# Sheet1.net
KiCad netlist of a schematic drawn in Altium Designer
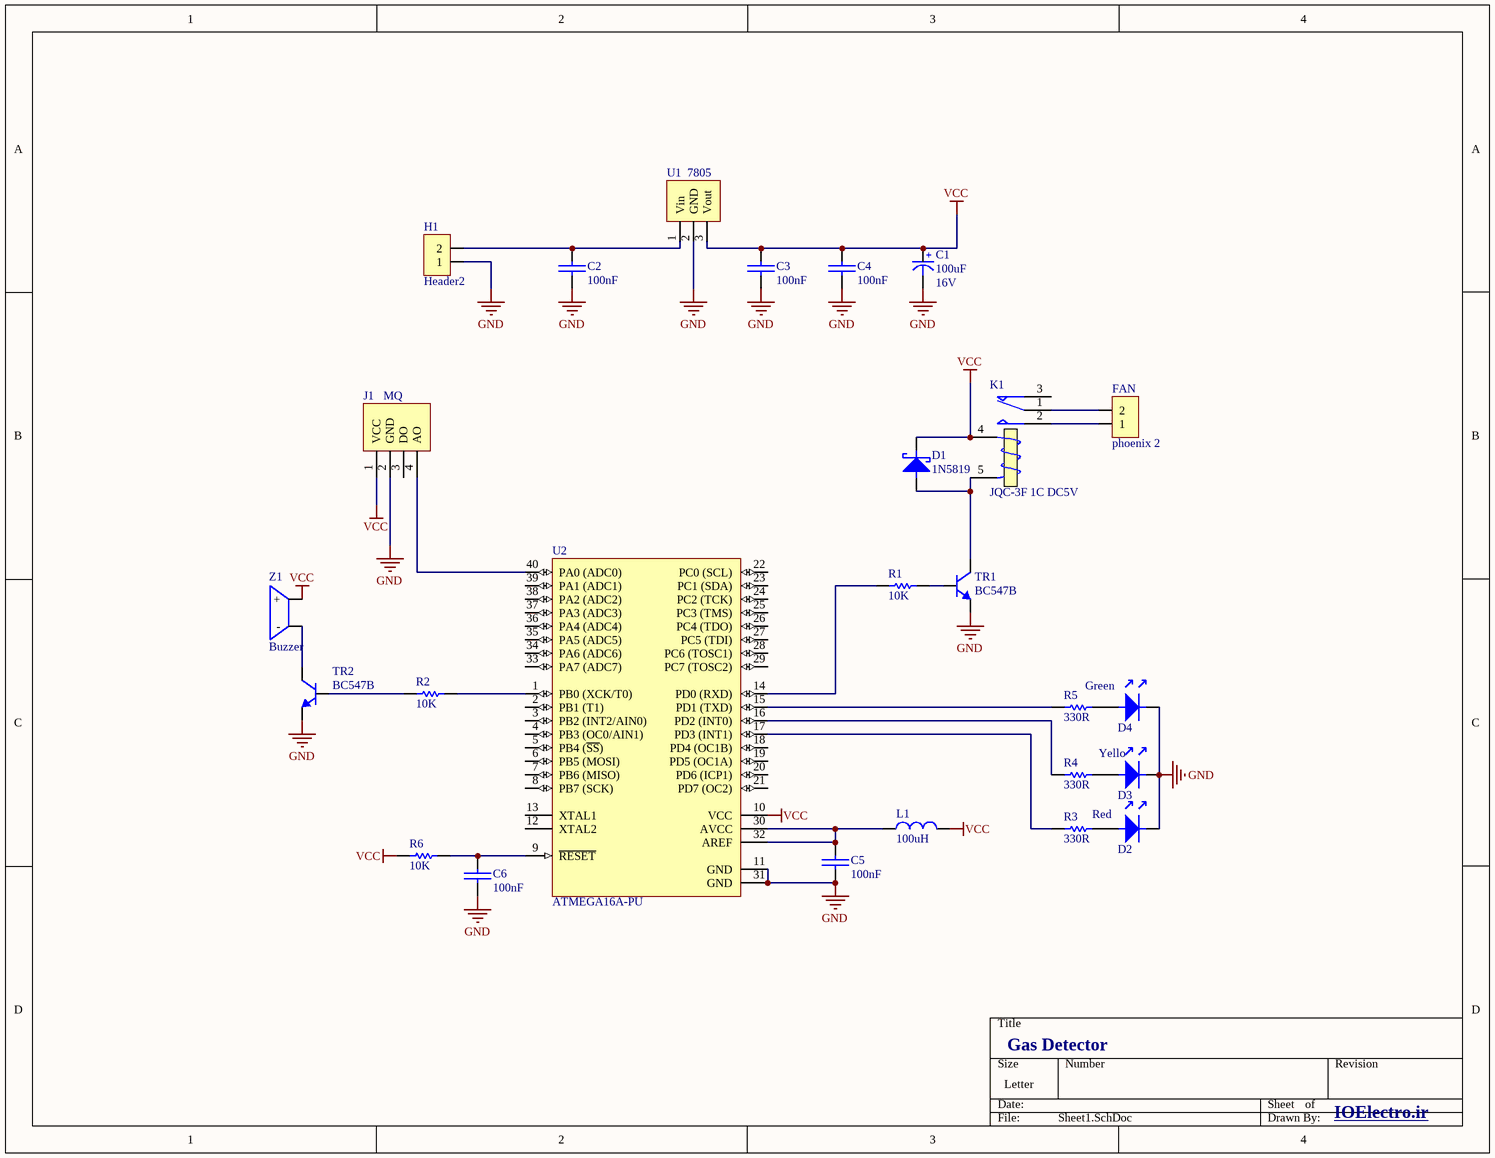
[diagram p0: Sheet1.SchDoc]

(export (version "E")
  (design (tool "Eeschema 10.0.6"))
  (components
    (comp (ref "C1")
      (value "100uF")
      (footprint "cap 03")
      (description "Polar Capacitor")
      (fields (field (name "VOLTAGE") "16V") (field (name "DESIGNER") "Saeid Jorablo"))
      (libsource (lib "My Library") (part "Cap-Polar"))
    )
    (comp (ref "C2")
      (value "100nF")
      (footprint "Cap - 100nF")
      (description "Bipolar Capacitor")
      (fields (field (name "VOLTAGE") "100V") (field (name "DESIGNER") "Saeid Jorablo"))
      (libsource (lib "My Library") (part "Cap-Bipolar"))
    )
    (comp (ref "C3")
      (value "100nF")
      (footprint "Cap - 100nF")
      (description "Bipolar Capacitor")
      (fields (field (name "VOLTAGE") "100V") (field (name "DESIGNER") "Saeid Jorablo"))
      (libsource (lib "My Library") (part "Cap-Bipolar"))
    )
    (comp (ref "C4")
      (value "100nF")
      (footprint "Cap - 100nF")
      (description "Bipolar Capacitor")
      (fields (field (name "VOLTAGE") "100V") (field (name "DESIGNER") "Saeid Jorablo"))
      (libsource (lib "My Library") (part "Cap-Bipolar"))
    )
    (comp (ref "C5")
      (value "100nF")
      (footprint "Cap - 100nF")
      (description "Bipolar Capacitor")
      (fields (field (name "VOLTAGE") "100V") (field (name "DESIGNER") "Saeid Jorablo"))
      (libsource (lib "My Library") (part "Cap-Bipolar"))
    )
    (comp (ref "C6")
      (value "100nF")
      (footprint "Cap - 100nF")
      (description "Bipolar Capacitor")
      (fields (field (name "VOLTAGE") "100V") (field (name "DESIGNER") "Saeid Jorablo"))
      (libsource (lib "My Library") (part "Cap-Bipolar"))
    )
    (comp (ref "D1")
      (value "1N5819")
      (footprint "Diode_Axial_Lead")
      (description "1N58 Series 600 mV 1 A 40 V Max Reverse Voltage Schottky Barrier Rectifier-DO-41")
      (fields (field (name "MANUFACTURER") "ON Semiconductor / Fairchild"))
      (libsource (lib "IOElectro") (part "1N5819"))
    )
    (comp (ref "D2") (value "Red") (footprint "LED5MM") (libsource (lib "MyLib") (part "LED")))
    (comp (ref "D3") (value "Yello") (footprint "LED5MM") (libsource (lib "MyLib") (part "LED")))
    (comp (ref "D4") (value "Green") (footprint "LED5MM") (libsource (lib "MyLib") (part "LED")))
    (comp (ref "FAN") (value "phoenix 2") (footprint "phonix-2") (libsource (lib "MyLib") (part "CONN-PH-2")))
    (comp (ref "H1") (value "Header2") (footprint "HEADER-2") (libsource (lib "MyLib") (part "HEADER-2")))
    (comp (ref "J1") (value "MQ") (footprint "MQ") (libsource (lib "MyLib") (part "MQ")))
    (comp (ref "K1")
      (value "JQC-3F 1C DC5V")
      (footprint "JQC-3F(T73)")
      (description "Relay Milon 5V 1Contact T73")
      (libsource (lib "IOElectro") (part "JQC-3F 1C DC5V"))
    )
    (comp (ref "L1") (value "100uH") (footprint "IND-DIP") (libsource (lib "MyLib") (part "Inductor")))
    (comp (ref "R1")
      (value "10K")
      (footprint "RES-DIP")
      (description "1/4 W DIP")
      (libsource (lib "Schlib") (part "RES-Dip"))
    )
    (comp (ref "R2")
      (value "10K")
      (footprint "RES-DIP")
      (description "1/4 W DIP")
      (libsource (lib "Schlib") (part "RES-Dip"))
    )
    (comp (ref "R3")
      (value "330R")
      (footprint "RES-DIP")
      (description "1/4 W DIP")
      (libsource (lib "Schlib") (part "RES-Dip"))
    )
    (comp (ref "R4")
      (value "330R")
      (footprint "RES-DIP")
      (description "1/4 W DIP")
      (libsource (lib "Schlib") (part "RES-Dip"))
    )
    (comp (ref "R5")
      (value "330R")
      (footprint "RES-DIP")
      (description "1/4 W DIP")
      (libsource (lib "Schlib") (part "RES-Dip"))
    )
    (comp (ref "R6")
      (value "10K")
      (footprint "RES-DIP")
      (description "1/4 W DIP")
      (libsource (lib "Schlib") (part "RES-Dip"))
    )
    (comp (ref "TR1")
      (value "BC547B")
      (footprint "TO-92")
      (fields (field (name "MANUFACTURER") "ON Semiconductor / Fairchild") (field (name "VOLTAGE") "40V"))
      (libsource (lib "MyLib") (part "BC547B"))
    )
    (comp (ref "TR2")
      (value "BC547B")
      (footprint "TO-92")
      (fields (field (name "MANUFACTURER") "ON Semiconductor / Fairchild") (field (name "VOLTAGE") "40V"))
      (libsource (lib "MyLib") (part "BC547B"))
    )
    (comp (ref "U1") (value "7805") (footprint "TO-220") (libsource (lib "MyLib") (part "7805")))
    (comp (ref "U2")
      (value "ATMEGA16A-PU")
      (footprint "DIP-40")
      (description "MCU 8-Bit ATmega AVR RISC 16KB Flash 3.3V/5V 40-Pin PDIP")
      (fields (field (name "MANUFACTURER") "Microchip / Atmel"))
      (libsource (lib "IOElectro") (part "ATMEGA16A-PU"))
    )
    (comp (ref "Z1") (value "Buzzer") (footprint "BUZZER-TMB12A05") (libsource (lib "MyLib") (part "BUZZER")))
  )
  (nets
    (net (code "1") (name "GND") (class "Default")
      (node (ref "C1") (pin "2") (pinfunction "-_2") (pintype "passive"))
      (node (ref "C2") (pin "2") (pinfunction "-_2") (pintype "passive"))
      (node (ref "C3") (pin "2") (pinfunction "-_2") (pintype "passive"))
      (node (ref "C4") (pin "2") (pinfunction "-_2") (pintype "passive"))
      (node (ref "C5") (pin "2") (pinfunction "-_2") (pintype "passive"))
      (node (ref "C6") (pin "2") (pinfunction "-_2") (pintype "passive"))
      (node (ref "D2") (pin "K") (pinfunction "K_K") (pintype "passive"))
      (node (ref "D3") (pin "K") (pinfunction "K_K") (pintype "passive"))
      (node (ref "D4") (pin "K") (pinfunction "K_K") (pintype "passive"))
      (node (ref "H1") (pin "1") (pinfunction "1_1") (pintype "passive"))
      (node (ref "J1") (pin "2") (pinfunction "GND_2") (pintype "passive"))
      (node (ref "TR1") (pin "3") (pinfunction "E_3") (pintype "passive"))
      (node (ref "TR2") (pin "3") (pinfunction "E_3") (pintype "passive"))
      (node (ref "U1") (pin "2") (pinfunction "GND_2") (pintype "passive"))
      (node (ref "U2") (pin "11") (pinfunction "GND_11") (pintype "power_in"))
      (node (ref "U2") (pin "31") (pinfunction "GND_31") (pintype "power_in"))
    )
    (net (code "2") (name "Net-(C2-+)") (class "Default")
      (node (ref "C2") (pin "1") (pinfunction "+_1") (pintype "passive"))
      (node (ref "H1") (pin "2") (pinfunction "2_2") (pintype "passive"))
      (node (ref "U1") (pin "1") (pinfunction "Vin_1") (pintype "passive"))
    )
    (net (code "3") (name "Net-(C5-+)") (class "Default")
      (node (ref "C5") (pin "1") (pinfunction "+_1") (pintype "passive"))
      (node (ref "L1") (pin "2") (pinfunction "2_2") (pintype "passive"))
      (node (ref "U2") (pin "30") (pinfunction "AVCC_30") (pintype "power_in"))
      (node (ref "U2") (pin "32") (pinfunction "AREF_32") (pintype "power_in"))
    )
    (net (code "4") (name "Net-(C6-+)") (class "Default")
      (node (ref "C6") (pin "1") (pinfunction "+_1") (pintype "passive"))
      (node (ref "R6") (pin "2") (pinfunction "2_2") (pintype "passive"))
      (node (ref "U2") (pin "9") (pinfunction "~{RESET}_9") (pintype "input"))
    )
    (net (code "5") (name "Net-(D2-PadA)") (class "Default")
      (node (ref "D2") (pin "A") (pinfunction "A_A") (pintype "passive"))
      (node (ref "R3") (pin "2") (pinfunction "2_2") (pintype "passive"))
    )
    (net (code "6") (name "Net-(D3-PadA)") (class "Default")
      (node (ref "D3") (pin "A") (pinfunction "A_A") (pintype "passive"))
      (node (ref "R4") (pin "2") (pinfunction "2_2") (pintype "passive"))
    )
    (net (code "7") (name "Net-(D4-PadA)") (class "Default")
      (node (ref "D4") (pin "A") (pinfunction "A_A") (pintype "passive"))
      (node (ref "R5") (pin "2") (pinfunction "2_2") (pintype "passive"))
    )
    (net (code "8") (name "Net-(J1-AO)") (class "Default")
      (node (ref "J1") (pin "4") (pinfunction "AO_4") (pintype "passive"))
      (node (ref "U2") (pin "40") (pinfunction "PA0_(ADC0)_40") (pintype "bidirectional"))
    )
    (net (code "9") (name "Net-(K1-COM)") (class "Default")
      (node (ref "FAN") (pin "2") (pinfunction "2_2") (pintype "passive"))
      (node (ref "K1") (pin "1") (pinfunction "COM_1") (pintype "passive"))
    )
    (net (code "10") (name "Net-(K1-NO)") (class "Default")
      (node (ref "FAN") (pin "1") (pinfunction "1_1") (pintype "passive"))
      (node (ref "K1") (pin "2") (pinfunction "NO_2") (pintype "passive"))
    )
    (net (code "11") (name "Net-(K1-T2)") (class "Default")
      (node (ref "D1") (pin "A") (pinfunction "A_A") (pintype "passive"))
      (node (ref "K1") (pin "5") (pinfunction "T2_5") (pintype "passive"))
      (node (ref "TR1") (pin "1") (pinfunction "C_1") (pintype "passive"))
    )
    (net (code "12") (name "Net-(TR1-B)") (class "Default")
      (node (ref "R1") (pin "2") (pinfunction "2_2") (pintype "passive"))
      (node (ref "TR1") (pin "2") (pinfunction "B_2") (pintype "passive"))
    )
    (net (code "13") (name "Net-(TR2-B)") (class "Default")
      (node (ref "R2") (pin "1") (pinfunction "1_1") (pintype "passive"))
      (node (ref "TR2") (pin "2") (pinfunction "B_2") (pintype "passive"))
    )
    (net (code "14") (name "Net-(TR2-C)") (class "Default")
      (node (ref "TR2") (pin "1") (pinfunction "C_1") (pintype "passive"))
      (node (ref "Z1") (pin "1") (pinfunction "-_1") (pintype "passive"))
    )
    (net (code "15") (name "Net-(U2-PB0_(XCK{slash}T0))") (class "Default")
      (node (ref "R2") (pin "2") (pinfunction "2_2") (pintype "passive"))
      (node (ref "U2") (pin "1") (pinfunction "PB0_(XCK/T0)_1") (pintype "bidirectional"))
    )
    (net (code "16") (name "Net-(U2-PD0_(RXD))") (class "Default")
      (node (ref "R1") (pin "1") (pinfunction "1_1") (pintype "passive"))
      (node (ref "U2") (pin "14") (pinfunction "PD0_(RXD)_14") (pintype "bidirectional"))
    )
    (net (code "17") (name "Net-(U2-PD1_(TXD))") (class "Default")
      (node (ref "R5") (pin "1") (pinfunction "1_1") (pintype "passive"))
      (node (ref "U2") (pin "15") (pinfunction "PD1_(TXD)_15") (pintype "bidirectional"))
    )
    (net (code "18") (name "Net-(U2-PD2_(INT0))") (class "Default")
      (node (ref "R4") (pin "1") (pinfunction "1_1") (pintype "passive"))
      (node (ref "U2") (pin "16") (pinfunction "PD2_(INT0)_16") (pintype "bidirectional"))
    )
    (net (code "19") (name "Net-(U2-PD3_(INT1))") (class "Default")
      (node (ref "R3") (pin "1") (pinfunction "1_1") (pintype "passive"))
      (node (ref "U2") (pin "17") (pinfunction "PD3_(INT1)_17") (pintype "bidirectional"))
    )
    (net (code "20") (name "VCC") (class "Default")
      (node (ref "C1") (pin "1") (pinfunction "+_1") (pintype "passive"))
      (node (ref "C3") (pin "1") (pinfunction "+_1") (pintype "passive"))
      (node (ref "C4") (pin "1") (pinfunction "+_1") (pintype "passive"))
      (node (ref "D1") (pin "K") (pinfunction "K_K") (pintype "passive"))
      (node (ref "J1") (pin "1") (pinfunction "VCC_1") (pintype "passive"))
      (node (ref "K1") (pin "4") (pinfunction "T1_4") (pintype "passive"))
      (node (ref "L1") (pin "1") (pinfunction "1_1") (pintype "passive"))
      (node (ref "R6") (pin "1") (pinfunction "1_1") (pintype "passive"))
      (node (ref "U1") (pin "3") (pinfunction "Vout_3") (pintype "passive"))
      (node (ref "U2") (pin "10") (pinfunction "VCC_10") (pintype "power_in"))
      (node (ref "Z1") (pin "2") (pinfunction "+_2") (pintype "passive"))
    )
    (net (code "21") (name "unconnected-(J1-DO-Pad3)") (class "Default")
      (node (ref "J1") (pin "3") (pinfunction "DO_3") (pintype "passive"))
    )
    (net (code "22") (name "unconnected-(K1-NC-Pad3)") (class "Default")
      (node (ref "K1") (pin "3") (pinfunction "NC_3") (pintype "passive"))
    )
    (net (code "23") (name "unconnected-(U2-PA1_(ADC1)-Pad39)") (class "Default")
      (node (ref "U2") (pin "39") (pinfunction "PA1_(ADC1)_39") (pintype "bidirectional"))
    )
    (net (code "24") (name "unconnected-(U2-PA2_(ADC2)-Pad38)") (class "Default")
      (node (ref "U2") (pin "38") (pinfunction "PA2_(ADC2)_38") (pintype "bidirectional"))
    )
    (net (code "25") (name "unconnected-(U2-PA3_(ADC3)-Pad37)") (class "Default")
      (node (ref "U2") (pin "37") (pinfunction "PA3_(ADC3)_37") (pintype "bidirectional"))
    )
    (net (code "26") (name "unconnected-(U2-PA4_(ADC4)-Pad36)") (class "Default")
      (node (ref "U2") (pin "36") (pinfunction "PA4_(ADC4)_36") (pintype "bidirectional"))
    )
    (net (code "27") (name "unconnected-(U2-PA5_(ADC5)-Pad35)") (class "Default")
      (node (ref "U2") (pin "35") (pinfunction "PA5_(ADC5)_35") (pintype "bidirectional"))
    )
    (net (code "28") (name "unconnected-(U2-PA6_(ADC6)-Pad34)") (class "Default")
      (node (ref "U2") (pin "34") (pinfunction "PA6_(ADC6)_34") (pintype "bidirectional"))
    )
    (net (code "29") (name "unconnected-(U2-PA7_(ADC7)-Pad33)") (class "Default")
      (node (ref "U2") (pin "33") (pinfunction "PA7_(ADC7)_33") (pintype "bidirectional"))
    )
    (net (code "30") (name "unconnected-(U2-PB1_(T1)-Pad2)") (class "Default")
      (node (ref "U2") (pin "2") (pinfunction "PB1_(T1)_2") (pintype "bidirectional"))
    )
    (net (code "31") (name "unconnected-(U2-PB2_(INT2{slash}AIN0)-Pad3)") (class "Default")
      (node (ref "U2") (pin "3") (pinfunction "PB2_(INT2/AIN0)_3") (pintype "bidirectional"))
    )
    (net (code "32") (name "unconnected-(U2-PB3_(OC0{slash}AIN1)-Pad4)") (class "Default")
      (node (ref "U2") (pin "4") (pinfunction "PB3_(OC0/AIN1)_4") (pintype "bidirectional"))
    )
    (net (code "33") (name "unconnected-(U2-PB4_(~{SS})-Pad5)") (class "Default")
      (node (ref "U2") (pin "5") (pinfunction "PB4_(~{SS})_5") (pintype "bidirectional"))
    )
    (net (code "34") (name "unconnected-(U2-PB5_(MOSI)-Pad6)") (class "Default")
      (node (ref "U2") (pin "6") (pinfunction "PB5_(MOSI)_6") (pintype "bidirectional"))
    )
    (net (code "35") (name "unconnected-(U2-PB6_(MISO)-Pad7)") (class "Default")
      (node (ref "U2") (pin "7") (pinfunction "PB6_(MISO)_7") (pintype "bidirectional"))
    )
    (net (code "36") (name "unconnected-(U2-PB7_(SCK)-Pad8)") (class "Default")
      (node (ref "U2") (pin "8") (pinfunction "PB7_(SCK)_8") (pintype "bidirectional"))
    )
    (net (code "37") (name "unconnected-(U2-PC0_(SCL)-Pad22)") (class "Default")
      (node (ref "U2") (pin "22") (pinfunction "PC0_(SCL)_22") (pintype "bidirectional"))
    )
    (net (code "38") (name "unconnected-(U2-PC1_(SDA)-Pad23)") (class "Default")
      (node (ref "U2") (pin "23") (pinfunction "PC1_(SDA)_23") (pintype "bidirectional"))
    )
    (net (code "39") (name "unconnected-(U2-PC2_(TCK)-Pad24)") (class "Default")
      (node (ref "U2") (pin "24") (pinfunction "PC2_(TCK)_24") (pintype "bidirectional"))
    )
    (net (code "40") (name "unconnected-(U2-PC3_(TMS)-Pad25)") (class "Default")
      (node (ref "U2") (pin "25") (pinfunction "PC3_(TMS)_25") (pintype "bidirectional"))
    )
    (net (code "41") (name "unconnected-(U2-PC4_(TDO)-Pad26)") (class "Default")
      (node (ref "U2") (pin "26") (pinfunction "PC4_(TDO)_26") (pintype "bidirectional"))
    )
    (net (code "42") (name "unconnected-(U2-PC5_(TDI)-Pad27)") (class "Default")
      (node (ref "U2") (pin "27") (pinfunction "PC5_(TDI)_27") (pintype "bidirectional"))
    )
    (net (code "43") (name "unconnected-(U2-PC6_(TOSC1)-Pad28)") (class "Default")
      (node (ref "U2") (pin "28") (pinfunction "PC6_(TOSC1)_28") (pintype "bidirectional"))
    )
    (net (code "44") (name "unconnected-(U2-PC7_(TOSC2)-Pad29)") (class "Default")
      (node (ref "U2") (pin "29") (pinfunction "PC7_(TOSC2)_29") (pintype "bidirectional"))
    )
    (net (code "45") (name "unconnected-(U2-PD4_(OC1B)-Pad18)") (class "Default")
      (node (ref "U2") (pin "18") (pinfunction "PD4_(OC1B)_18") (pintype "bidirectional"))
    )
    (net (code "46") (name "unconnected-(U2-PD5_(OC1A)-Pad19)") (class "Default")
      (node (ref "U2") (pin "19") (pinfunction "PD5_(OC1A)_19") (pintype "bidirectional"))
    )
    (net (code "47") (name "unconnected-(U2-PD6_(ICP1)-Pad20)") (class "Default")
      (node (ref "U2") (pin "20") (pinfunction "PD6_(ICP1)_20") (pintype "bidirectional"))
    )
    (net (code "48") (name "unconnected-(U2-PD7_(OC2)-Pad21)") (class "Default")
      (node (ref "U2") (pin "21") (pinfunction "PD7_(OC2)_21") (pintype "bidirectional"))
    )
    (net (code "49") (name "unconnected-(U2-XTAL1-Pad13)") (class "Default")
      (node (ref "U2") (pin "13") (pinfunction "XTAL1_13") (pintype "passive"))
    )
    (net (code "50") (name "unconnected-(U2-XTAL2-Pad12)") (class "Default")
      (node (ref "U2") (pin "12") (pinfunction "XTAL2_12") (pintype "passive"))
    )
  )
)
